# GF_RemoteDoorOpener_RX.net
KiCad netlist of a schematic drawn in EAGLE
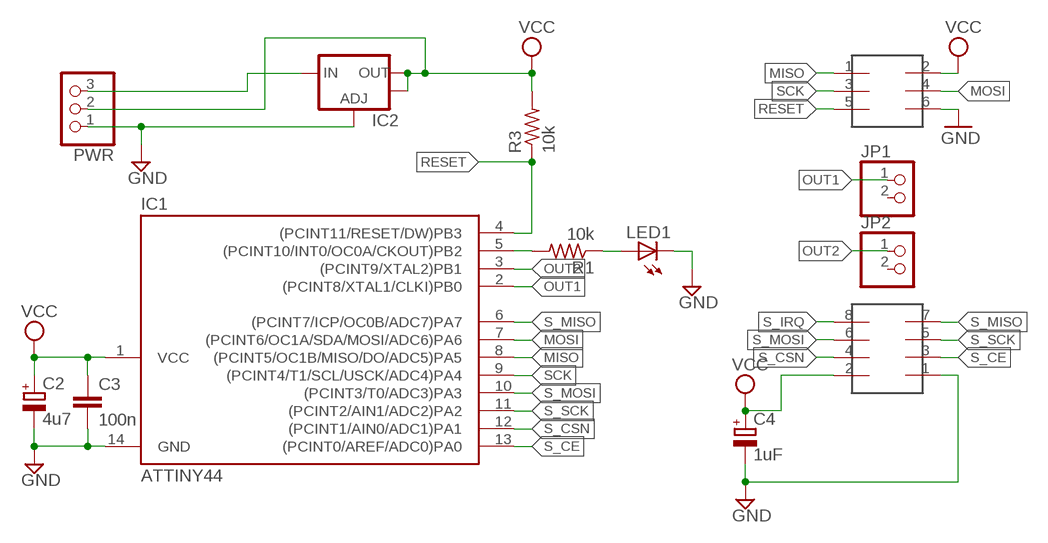
[diagram p0: schematic, sheet 1]

(export (version "E")
  (design (tool "Eeschema 10.0.6"))
  (components
    (comp (ref "C2")
      (value "4u7")
      (footprint "eagle-import:SMC_A")
      (libsource (lib "eagle-import") (part "CPOL-EUSMCA"))
    )
    (comp (ref "C3")
      (value "100n")
      (footprint "eagle-import:C0603")
      (libsource (lib "eagle-import") (part "C-EUC0603"))
    )
    (comp (ref "C4")
      (value "1uF")
      (footprint "eagle-import:SMC_A")
      (libsource (lib "eagle-import") (part "CPOL-EUSMCA"))
    )
    (comp (ref "IC1")
      (value "ATTINY44")
      (footprint "eagle-import:SOIC14")
      (libsource (lib "eagle-import") (part "ATTINY24/44/84-SSU"))
    )
    (comp (ref "IC2")
      (value "V_REG_LM1117SOT223")
      (footprint "eagle-import:SOT223")
      (libsource (lib "eagle-import") (part "V_REG_LM1117SOT223"))
    )
    (comp (ref "ISP")
      (value "2X3HEADER")
      (footprint "eagle-import:2X3_SMD")
      (libsource (lib "eagle-import") (part "2X3HEADER"))
    )
    (comp (ref "JP1")
      (value "PINHD-1X2")
      (footprint "eagle-import:1X02")
      (libsource (lib "eagle-import") (part "PINHD-1X2"))
    )
    (comp (ref "JP2")
      (value "PINHD-1X2")
      (footprint "eagle-import:1X02")
      (libsource (lib "eagle-import") (part "PINHD-1X2"))
    )
    (comp (ref "LED1")
      (value "LEDCHIPLED_1206")
      (footprint "eagle-import:CHIPLED_1206")
      (libsource (lib "eagle-import") (part "LEDCHIPLED_1206"))
    )
    (comp (ref "PWR")
      (value "PINHD-1X3")
      (footprint "eagle-import:1X03")
      (libsource (lib "eagle-import") (part "PINHD-1X3"))
    )
    (comp (ref "R1")
      (value "10k")
      (footprint "eagle-import:R0603")
      (libsource (lib "eagle-import") (part "R-US_R0603"))
    )
    (comp (ref "R3")
      (value "10k")
      (footprint "eagle-import:R0603")
      (libsource (lib "eagle-import") (part "R-US_R0603"))
    )
    (comp (ref "U$2")
      (value "2X4HEADER")
      (footprint "eagle-import:2X4_SMD")
      (libsource (lib "eagle-import") (part "2X4HEADER"))
    )
  )
  (nets
    (net (code "1") (name "GND") (class "Default")
      (node (ref "C2") (pin "-") (pinfunction "-_-") (pintype "passive"))
      (node (ref "C3") (pin "2") (pinfunction "2_2") (pintype "passive"))
      (node (ref "C4") (pin "-") (pinfunction "-_-") (pintype "passive"))
      (node (ref "IC1") (pin "14") (pinfunction "GND_14") (pintype "power_in"))
      (node (ref "IC2") (pin "1") (pinfunction "ADJ_1") (pintype "input"))
      (node (ref "ISP") (pin "6") (pinfunction "P$6_6") (pintype "bidirectional"))
      (node (ref "LED1") (pin "C") (pinfunction "C_C") (pintype "passive"))
      (node (ref "PWR") (pin "1") (pinfunction "1_1") (pintype "passive"))
      (node (ref "U$2") (pin "1") (pinfunction "P$1_1") (pintype "bidirectional"))
    )
    (net (code "2") (name "MISO") (class "Default")
      (node (ref "IC1") (pin "8") (pinfunction "(PCINT5/OC1B/MISO/DO/ADC5)PA5_8") (pintype "bidirectional"))
      (node (ref "ISP") (pin "1") (pinfunction "P$1_1") (pintype "bidirectional"))
    )
    (net (code "3") (name "MOSI") (class "Default")
      (node (ref "IC1") (pin "7") (pinfunction "(PCINT6/OC1A/SDA/MOSI/ADC6)PA6_7") (pintype "bidirectional"))
      (node (ref "ISP") (pin "4") (pinfunction "P$4_4") (pintype "bidirectional"))
    )
    (net (code "4") (name "Net-(IC1-(PCINT10{slash}INT0{slash}OC0A{slash}CKOUT)PB2)") (class "Default")
      (node (ref "IC1") (pin "5") (pinfunction "(PCINT10/INT0/OC0A/CKOUT)PB2_5") (pintype "bidirectional"))
      (node (ref "R1") (pin "2") (pinfunction "2_2") (pintype "passive"))
    )
    (net (code "5") (name "Net-(IC2-IN)") (class "Default")
      (node (ref "IC2") (pin "3") (pinfunction "IN_3") (pintype "input"))
      (node (ref "PWR") (pin "3") (pinfunction "3_3") (pintype "passive"))
    )
    (net (code "6") (name "Net-(LED1-PadA)") (class "Default")
      (node (ref "LED1") (pin "A") (pinfunction "A_A") (pintype "passive"))
      (node (ref "R1") (pin "1") (pinfunction "1_1") (pintype "passive"))
    )
    (net (code "7") (name "OUT1") (class "Default")
      (node (ref "IC1") (pin "2") (pinfunction "(PCINT8/XTAL1/CLKI)PB0_2") (pintype "bidirectional"))
      (node (ref "JP1") (pin "1") (pinfunction "1_1") (pintype "passive"))
    )
    (net (code "8") (name "OUT2") (class "Default")
      (node (ref "IC1") (pin "3") (pinfunction "(PCINT9/XTAL2)PB1_3") (pintype "bidirectional"))
      (node (ref "JP2") (pin "1") (pinfunction "1_1") (pintype "passive"))
    )
    (net (code "9") (name "RESET") (class "Default")
      (node (ref "IC1") (pin "4") (pinfunction "(PCINT11/RESET/DW)PB3_4") (pintype "bidirectional"))
      (node (ref "ISP") (pin "5") (pinfunction "P$5_5") (pintype "bidirectional"))
      (node (ref "R3") (pin "1") (pinfunction "1_1") (pintype "passive"))
    )
    (net (code "10") (name "SCK") (class "Default")
      (node (ref "IC1") (pin "9") (pinfunction "(PCINT4/T1/SCL/USCK/ADC4)PA4_9") (pintype "bidirectional"))
      (node (ref "ISP") (pin "3") (pinfunction "P$3_3") (pintype "bidirectional"))
    )
    (net (code "11") (name "S_CE") (class "Default")
      (node (ref "IC1") (pin "13") (pinfunction "(PCINT0/AREF/ADC0)PA0_13") (pintype "bidirectional"))
      (node (ref "U$2") (pin "3") (pinfunction "P$3_3") (pintype "bidirectional"))
    )
    (net (code "12") (name "S_CSN") (class "Default")
      (node (ref "IC1") (pin "12") (pinfunction "(PCINT1/AIN0/ADC1)PA1_12") (pintype "bidirectional"))
      (node (ref "U$2") (pin "4") (pinfunction "P$4_4") (pintype "bidirectional"))
    )
    (net (code "13") (name "S_IRQ") (class "Default")
      (node (ref "U$2") (pin "8") (pinfunction "P$8_8") (pintype "bidirectional"))
    )
    (net (code "14") (name "S_MISO") (class "Default")
      (node (ref "IC1") (pin "6") (pinfunction "(PCINT7/ICP/OC0B/ADC7)PA7_6") (pintype "bidirectional"))
      (node (ref "U$2") (pin "7") (pinfunction "P$7_7") (pintype "bidirectional"))
    )
    (net (code "15") (name "S_MOSI") (class "Default")
      (node (ref "IC1") (pin "10") (pinfunction "(PCINT3/T0/ADC3)PA3_10") (pintype "bidirectional"))
      (node (ref "U$2") (pin "6") (pinfunction "P$6_6") (pintype "bidirectional"))
    )
    (net (code "16") (name "S_SCK") (class "Default")
      (node (ref "IC1") (pin "11") (pinfunction "(PCINT2/AIN1/ADC2)PA2_11") (pintype "bidirectional"))
      (node (ref "U$2") (pin "5") (pinfunction "P$5_5") (pintype "bidirectional"))
    )
    (net (code "17") (name "VCC") (class "Default")
      (node (ref "C2") (pin "+") (pinfunction "+_+") (pintype "passive"))
      (node (ref "C3") (pin "1") (pinfunction "1_1") (pintype "passive"))
      (node (ref "C4") (pin "+") (pinfunction "+_+") (pintype "passive"))
      (node (ref "IC1") (pin "1") (pinfunction "VCC_1") (pintype "power_in"))
      (node (ref "IC2") (pin "2") (pinfunction "OUT_2") (pintype "output"))
      (node (ref "IC2") (pin "4") (pinfunction "OUT_4") (pintype "output"))
      (node (ref "ISP") (pin "2") (pinfunction "P$2_2") (pintype "bidirectional"))
      (node (ref "PWR") (pin "2") (pinfunction "2_2") (pintype "passive"))
      (node (ref "R3") (pin "2") (pinfunction "2_2") (pintype "passive"))
      (node (ref "U$2") (pin "2") (pinfunction "P$2_2") (pintype "bidirectional"))
    )
    (net (code "18") (name "unconnected-(JP1-Pad2)") (class "Default")
      (node (ref "JP1") (pin "2") (pinfunction "2_2") (pintype "passive"))
    )
    (net (code "19") (name "unconnected-(JP2-Pad2)") (class "Default")
      (node (ref "JP2") (pin "2") (pinfunction "2_2") (pintype "passive"))
    )
  )
)
